# Escorna_CPU_2_00.net
KiCad netlist of a schematic drawn in EAGLE
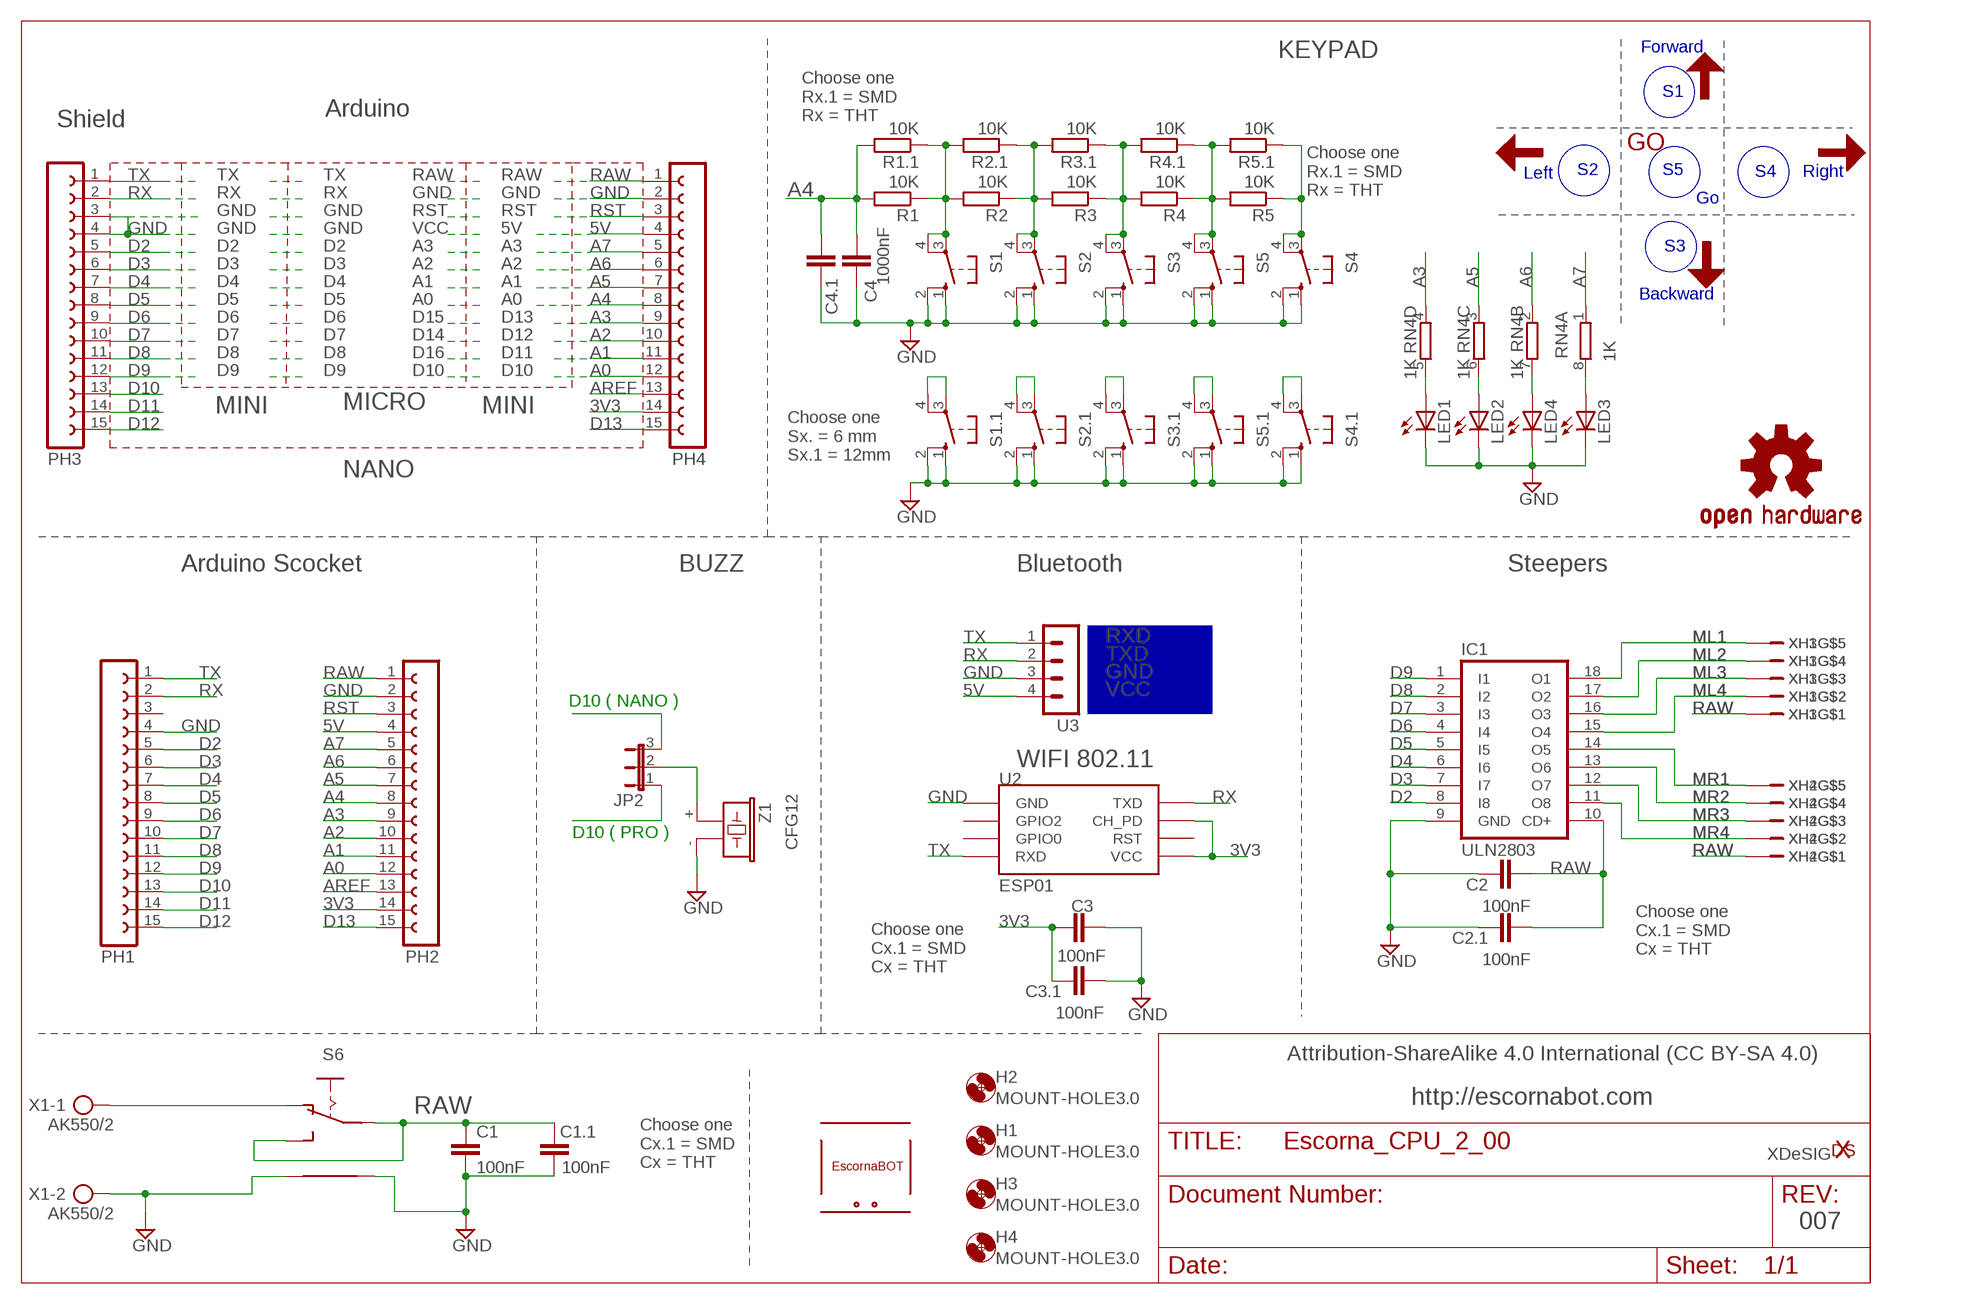
[diagram p0: schematic, sheet 1]

(export (version "E")
  (design (tool "Eeschema 10.0.6"))
  (components
    (comp (ref "C1")
      (value "100nF")
      (footprint "eagle-import:C025-025X050")
      (libsource (lib "eagle-import") (part "C-EU025-025X050"))
    )
    (comp (ref "C1.1")
      (value "100nF")
      (footprint "eagle-import:C0603")
      (libsource (lib "eagle-import") (part "C-EUC0603"))
    )
    (comp (ref "C2")
      (value "100nF")
      (footprint "eagle-import:C025-025X050")
      (libsource (lib "eagle-import") (part "C-EU025-025X050"))
    )
    (comp (ref "C2.1")
      (value "100nF")
      (footprint "eagle-import:C0603")
      (libsource (lib "eagle-import") (part "C-EUC0603"))
    )
    (comp (ref "C3")
      (value "100nF")
      (footprint "eagle-import:C025-025X050")
      (libsource (lib "eagle-import") (part "C-EU025-025X050"))
    )
    (comp (ref "C3.1")
      (value "100nF")
      (footprint "eagle-import:C0603")
      (libsource (lib "eagle-import") (part "C-EUC0603"))
    )
    (comp (ref "C4")
      (value "1000nF")
      (footprint "eagle-import:C025-025X050")
      (libsource (lib "eagle-import") (part "C-EU025-025X050"))
    )
    (comp (ref "C4.1")
      (value "100nF")
      (footprint "eagle-import:C0603")
      (libsource (lib "eagle-import") (part "C-EUC0603"))
    )
    (comp (ref "ESC")
      (value "ESCORNABOT")
      (footprint "eagle-import:ESCORNA_PEQUE")
      (libsource (lib "eagle-import") (part "ESCORNABOT"))
    )
    (comp (ref "H1")
      (value "MOUNT-HOLE3.0")
      (footprint "eagle-import:3,0")
      (libsource (lib "eagle-import") (part "MOUNT-HOLE3.0"))
    )
    (comp (ref "H2")
      (value "MOUNT-HOLE3.0")
      (footprint "eagle-import:3,0")
      (libsource (lib "eagle-import") (part "MOUNT-HOLE3.0"))
    )
    (comp (ref "H3")
      (value "MOUNT-HOLE3.0")
      (footprint "eagle-import:3,0")
      (libsource (lib "eagle-import") (part "MOUNT-HOLE3.0"))
    )
    (comp (ref "H4")
      (value "MOUNT-HOLE3.0")
      (footprint "eagle-import:3,0")
      (libsource (lib "eagle-import") (part "MOUNT-HOLE3.0"))
    )
    (comp (ref "IC1")
      (value "ULN2803")
      (footprint "eagle-import:DIL18")
      (libsource (lib "eagle-import") (part "ULN2803A{dblquote}"))
    )
    (comp (ref "JP2")
      (value "JP2E")
      (footprint "eagle-import:JP2")
      (libsource (lib "eagle-import") (part "JP2E"))
    )
    (comp (ref "LED1")
      (value "LED_ESML0603")
      (footprint "eagle-import:LED_SML0603")
      (libsource (lib "eagle-import") (part "LED_ESML0603"))
    )
    (comp (ref "LED2")
      (value "LED_ESML0603")
      (footprint "eagle-import:LED_SML0603")
      (libsource (lib "eagle-import") (part "LED_ESML0603"))
    )
    (comp (ref "LED3")
      (value "LED_ESML0603")
      (footprint "eagle-import:LED_SML0603")
      (libsource (lib "eagle-import") (part "LED_ESML0603"))
    )
    (comp (ref "LED4")
      (value "LED_ESML0603")
      (footprint "eagle-import:LED_SML0603")
      (libsource (lib "eagle-import") (part "LED_ESML0603"))
    )
    (comp (ref "LOGO1")
      (value "OSHW-LOGOS")
      (footprint "eagle-import:OSHW-LOGO-S")
      (libsource (lib "eagle-import") (part "OSHW-LOGOS"))
    )
    (comp (ref "PH1")
      (value "FE15-1")
      (footprint "eagle-import:FE15")
      (libsource (lib "eagle-import") (part "FE15-1"))
    )
    (comp (ref "PH2")
      (value "FE15-1")
      (footprint "eagle-import:FE15")
      (libsource (lib "eagle-import") (part "FE15-1"))
    )
    (comp (ref "PH3")
      (value "FE15-1")
      (footprint "eagle-import:FE15")
      (libsource (lib "eagle-import") (part "FE15-1"))
    )
    (comp (ref "PH4")
      (value "FE15-1")
      (footprint "eagle-import:FE15")
      (libsource (lib "eagle-import") (part "FE15-1"))
    )
    (comp (ref "R1")
      (value "10K")
      (footprint "eagle-import:0204_7")
      (libsource (lib "eagle-import") (part "R-EU_0204/7"))
    )
    (comp (ref "R1.1")
      (value "10K")
      (footprint "eagle-import:R0603")
      (libsource (lib "eagle-import") (part "R-EU_R0603"))
    )
    (comp (ref "R2")
      (value "10K")
      (footprint "eagle-import:0204_7")
      (libsource (lib "eagle-import") (part "R-EU_0204/7"))
    )
    (comp (ref "R2.1")
      (value "10K")
      (footprint "eagle-import:R0603")
      (libsource (lib "eagle-import") (part "R-EU_R0603"))
    )
    (comp (ref "R3")
      (value "10K")
      (footprint "eagle-import:0204_7")
      (libsource (lib "eagle-import") (part "R-EU_0204/7"))
    )
    (comp (ref "R3.1")
      (value "10K")
      (footprint "eagle-import:R0603")
      (libsource (lib "eagle-import") (part "R-EU_R0603"))
    )
    (comp (ref "R4")
      (value "10K")
      (footprint "eagle-import:0204_7")
      (libsource (lib "eagle-import") (part "R-EU_0204/7"))
    )
    (comp (ref "R4.1")
      (value "10K")
      (footprint "eagle-import:R0603")
      (libsource (lib "eagle-import") (part "R-EU_R0603"))
    )
    (comp (ref "R5")
      (value "10K")
      (footprint "eagle-import:0204_7")
      (libsource (lib "eagle-import") (part "R-EU_0204/7"))
    )
    (comp (ref "R5.1")
      (value "10K")
      (footprint "eagle-import:R0603")
      (libsource (lib "eagle-import") (part "R-EU_R0603"))
    )
    (comp (ref "RN4")
      (value "1K")
      (footprint "eagle-import:CAY16")
      (libsource (lib "eagle-import") (part "4R-NCAY16"))
    )
    (comp (ref "S1")
      (value "10-XX")
      (footprint "eagle-import:B3F-10XX")
      (fields (field (name "MPN") "B3F-1000"))
      (libsource (lib "eagle-import") (part "10-XX"))
    )
    (comp (ref "S1.1")
      (value "40-XX")
      (footprint "eagle-import:B3F40XX_NH")
      (libsource (lib "eagle-import") (part "40-XX"))
    )
    (comp (ref "S2")
      (value "10-XX")
      (footprint "eagle-import:B3F-10XX")
      (fields (field (name "MPN") "B3F-1000"))
      (libsource (lib "eagle-import") (part "10-XX"))
    )
    (comp (ref "S2.1")
      (value "40-XX")
      (footprint "eagle-import:B3F40XX_NH")
      (libsource (lib "eagle-import") (part "40-XX"))
    )
    (comp (ref "S3")
      (value "10-XX")
      (footprint "eagle-import:B3F-10XX")
      (fields (field (name "MPN") "B3F-1000"))
      (libsource (lib "eagle-import") (part "10-XX"))
    )
    (comp (ref "S3.1")
      (value "40-XX")
      (footprint "eagle-import:B3F40XX_NH")
      (libsource (lib "eagle-import") (part "40-XX"))
    )
    (comp (ref "S4")
      (value "10-XX")
      (footprint "eagle-import:B3F-10XX")
      (fields (field (name "MPN") "B3F-1000"))
      (libsource (lib "eagle-import") (part "10-XX"))
    )
    (comp (ref "S4.1")
      (value "40-XX")
      (footprint "eagle-import:B3F40XX_NH")
      (libsource (lib "eagle-import") (part "40-XX"))
    )
    (comp (ref "S5")
      (value "10-XX")
      (footprint "eagle-import:B3F-10XX")
      (fields (field (name "MPN") "B3F-1000"))
      (libsource (lib "eagle-import") (part "10-XX"))
    )
    (comp (ref "S5.1")
      (value "40-XX")
      (footprint "eagle-import:B3F40XX_NH")
      (libsource (lib "eagle-import") (part "40-XX"))
    )
    (comp (ref "S6")
      (value "SK12F14D")
      (footprint "eagle-import:SK-12D07")
      (libsource (lib "eagle-import") (part "SK12F14D"))
    )
    (comp (ref "U$4")
      (value "FRECHA")
      (footprint "eagle-import:FRECHA")
      (libsource (lib "eagle-import") (part "FRECHA"))
    )
    (comp (ref "U$7")
      (value "FRECHA")
      (footprint "eagle-import:FRECHA")
      (libsource (lib "eagle-import") (part "FRECHA"))
    )
    (comp (ref "U$8")
      (value "FRECHA")
      (footprint "eagle-import:FRECHA")
      (libsource (lib "eagle-import") (part "FRECHA"))
    )
    (comp (ref "U$9")
      (value "FRECHA")
      (footprint "eagle-import:FRECHA")
      (libsource (lib "eagle-import") (part "FRECHA"))
    )
    (comp (ref "U$10")
      (value "GO")
      (footprint "eagle-import:VALE")
      (libsource (lib "eagle-import") (part "GO"))
    )
    (comp (ref "U2")
      (value "ESP01")
      (footprint "eagle-import:ESP01")
      (libsource (lib "eagle-import") (part "ESP01"))
    )
    (comp (ref "U3")
      (value "MA04-1")
      (footprint "eagle-import:MA04-1")
      (libsource (lib "eagle-import") (part "MA04-1"))
    )
    (comp (ref "X1")
      (value "AK550/2")
      (footprint "eagle-import:AK550_2")
      (libsource (lib "eagle-import") (part "AK550/2"))
    )
    (comp (ref "XDS1")
      (value "XDESIG")
      (footprint "eagle-import:XDESIG_CU_2")
      (libsource (lib "eagle-import") (part "XDESIG"))
    )
    (comp (ref "XH1")
      (value "B5B-XH-A")
      (footprint "eagle-import:B5B-XH-A")
      (libsource (lib "eagle-import") (part "B5B-XH-A"))
    )
    (comp (ref "XH2")
      (value "B5B-XH-A")
      (footprint "eagle-import:B5B-XH-A")
      (libsource (lib "eagle-import") (part "B5B-XH-A"))
    )
    (comp (ref "XH3")
      (value "B5B-XH-A")
      (footprint "eagle-import:B5B-XH-A")
      (libsource (lib "eagle-import") (part "B5B-XH-A"))
    )
    (comp (ref "XH4")
      (value "B5B-XH-A")
      (footprint "eagle-import:B5B-XH-A")
      (libsource (lib "eagle-import") (part "B5B-XH-A"))
    )
    (comp (ref "Z1")
      (value "CFG12")
      (footprint "eagle-import:F_CM12P")
      (libsource (lib "eagle-import") (part "F/CM12P"))
    )
  )
  (nets
    (net (code "1") (name "/3V3") (class "Default")
      (node (ref "C3") (pin "1") (pinfunction "1_1") (pintype "passive"))
      (node (ref "C3.1") (pin "1") (pinfunction "1_1") (pintype "passive"))
      (node (ref "PH2") (pin "14") (pinfunction "14_14") (pintype "passive"))
      (node (ref "PH4") (pin "14") (pinfunction "14_14") (pintype "passive"))
      (node (ref "U2") (pin "CH_PD") (pinfunction "CH_PD_CH_PD") (pintype "bidirectional"))
      (node (ref "U2") (pin "VCC") (pinfunction "VCC_VCC") (pintype "bidirectional"))
    )
    (net (code "2") (name "/5V") (class "Default")
      (node (ref "PH2") (pin "4") (pinfunction "4_4") (pintype "passive"))
      (node (ref "PH4") (pin "4") (pinfunction "4_4") (pintype "passive"))
      (node (ref "U3") (pin "4") (pinfunction "4_4") (pintype "passive"))
    )
    (net (code "3") (name "/A0") (class "Default")
      (node (ref "JP2") (pin "1") (pinfunction "1_1") (pintype "passive"))
      (node (ref "PH2") (pin "12") (pinfunction "12_12") (pintype "passive"))
      (node (ref "PH4") (pin "12") (pinfunction "12_12") (pintype "passive"))
    )
    (net (code "4") (name "/A1") (class "Default")
      (node (ref "PH2") (pin "11") (pinfunction "11_11") (pintype "passive"))
      (node (ref "PH4") (pin "11") (pinfunction "11_11") (pintype "passive"))
    )
    (net (code "5") (name "/A2") (class "Default")
      (node (ref "PH2") (pin "10") (pinfunction "10_10") (pintype "passive"))
      (node (ref "PH4") (pin "10") (pinfunction "10_10") (pintype "passive"))
    )
    (net (code "6") (name "/A3") (class "Default")
      (node (ref "PH2") (pin "9") (pinfunction "9_9") (pintype "passive"))
      (node (ref "PH4") (pin "9") (pinfunction "9_9") (pintype "passive"))
      (node (ref "RN4") (pin "4") (pinfunction "1_4") (pintype "passive"))
    )
    (net (code "7") (name "/A4") (class "Default")
      (node (ref "C4") (pin "2") (pinfunction "2_2") (pintype "passive"))
      (node (ref "C4.1") (pin "2") (pinfunction "2_2") (pintype "passive"))
      (node (ref "PH2") (pin "8") (pinfunction "8_8") (pintype "passive"))
      (node (ref "PH4") (pin "8") (pinfunction "8_8") (pintype "passive"))
      (node (ref "R1") (pin "2") (pinfunction "2_2") (pintype "passive"))
      (node (ref "R1.1") (pin "2") (pinfunction "2_2") (pintype "passive"))
    )
    (net (code "8") (name "/A5") (class "Default")
      (node (ref "PH2") (pin "7") (pinfunction "7_7") (pintype "passive"))
      (node (ref "PH4") (pin "7") (pinfunction "7_7") (pintype "passive"))
      (node (ref "RN4") (pin "3") (pinfunction "1_3") (pintype "passive"))
    )
    (net (code "9") (name "/A6") (class "Default")
      (node (ref "PH2") (pin "6") (pinfunction "6_6") (pintype "passive"))
      (node (ref "PH4") (pin "6") (pinfunction "6_6") (pintype "passive"))
      (node (ref "RN4") (pin "2") (pinfunction "1_2") (pintype "passive"))
    )
    (net (code "10") (name "/A7") (class "Default")
      (node (ref "PH2") (pin "5") (pinfunction "5_5") (pintype "passive"))
      (node (ref "PH4") (pin "5") (pinfunction "5_5") (pintype "passive"))
      (node (ref "RN4") (pin "1") (pinfunction "1_1") (pintype "passive"))
    )
    (net (code "11") (name "/AREF") (class "Default")
      (node (ref "PH2") (pin "13") (pinfunction "13_13") (pintype "passive"))
      (node (ref "PH4") (pin "13") (pinfunction "13_13") (pintype "passive"))
    )
    (net (code "12") (name "/D2") (class "Default")
      (node (ref "IC1") (pin "8") (pinfunction "I8_8") (pintype "input"))
      (node (ref "PH1") (pin "5") (pinfunction "5_5") (pintype "passive"))
      (node (ref "PH3") (pin "5") (pinfunction "5_5") (pintype "passive"))
    )
    (net (code "13") (name "/D3") (class "Default")
      (node (ref "IC1") (pin "7") (pinfunction "I7_7") (pintype "input"))
      (node (ref "PH1") (pin "6") (pinfunction "6_6") (pintype "passive"))
      (node (ref "PH3") (pin "6") (pinfunction "6_6") (pintype "passive"))
    )
    (net (code "14") (name "/D4") (class "Default")
      (node (ref "IC1") (pin "6") (pinfunction "I6_6") (pintype "input"))
      (node (ref "PH1") (pin "7") (pinfunction "7_7") (pintype "passive"))
      (node (ref "PH3") (pin "7") (pinfunction "7_7") (pintype "passive"))
    )
    (net (code "15") (name "/D5") (class "Default")
      (node (ref "IC1") (pin "5") (pinfunction "I5_5") (pintype "input"))
      (node (ref "PH1") (pin "8") (pinfunction "8_8") (pintype "passive"))
      (node (ref "PH3") (pin "8") (pinfunction "8_8") (pintype "passive"))
    )
    (net (code "16") (name "/D6") (class "Default")
      (node (ref "IC1") (pin "4") (pinfunction "I4_4") (pintype "input"))
      (node (ref "PH1") (pin "9") (pinfunction "9_9") (pintype "passive"))
      (node (ref "PH3") (pin "9") (pinfunction "9_9") (pintype "passive"))
    )
    (net (code "17") (name "/D7") (class "Default")
      (node (ref "IC1") (pin "3") (pinfunction "I3_3") (pintype "input"))
      (node (ref "PH1") (pin "10") (pinfunction "10_10") (pintype "passive"))
      (node (ref "PH3") (pin "10") (pinfunction "10_10") (pintype "passive"))
    )
    (net (code "18") (name "/D8") (class "Default")
      (node (ref "IC1") (pin "2") (pinfunction "I2_2") (pintype "input"))
      (node (ref "PH1") (pin "11") (pinfunction "11_11") (pintype "passive"))
      (node (ref "PH3") (pin "11") (pinfunction "11_11") (pintype "passive"))
    )
    (net (code "19") (name "/D9") (class "Default")
      (node (ref "IC1") (pin "1") (pinfunction "I1_1") (pintype "input"))
      (node (ref "PH1") (pin "12") (pinfunction "12_12") (pintype "passive"))
      (node (ref "PH3") (pin "12") (pinfunction "12_12") (pintype "passive"))
    )
    (net (code "20") (name "/D10") (class "Default")
      (node (ref "JP2") (pin "3") (pinfunction "3_3") (pintype "passive"))
      (node (ref "PH1") (pin "13") (pinfunction "13_13") (pintype "passive"))
      (node (ref "PH3") (pin "13") (pinfunction "13_13") (pintype "passive"))
    )
    (net (code "21") (name "/D11") (class "Default")
      (node (ref "PH1") (pin "14") (pinfunction "14_14") (pintype "passive"))
      (node (ref "PH3") (pin "14") (pinfunction "14_14") (pintype "passive"))
    )
    (net (code "22") (name "/D12") (class "Default")
      (node (ref "PH1") (pin "15") (pinfunction "15_15") (pintype "passive"))
      (node (ref "PH3") (pin "15") (pinfunction "15_15") (pintype "passive"))
    )
    (net (code "23") (name "/D13") (class "Default")
      (node (ref "PH2") (pin "15") (pinfunction "15_15") (pintype "passive"))
      (node (ref "PH4") (pin "15") (pinfunction "15_15") (pintype "passive"))
    )
    (net (code "24") (name "/ML1") (class "Default")
      (node (ref "IC1") (pin "18") (pinfunction "O1_18") (pintype "open_collector"))
      (node (ref "XH1") (pin "P$5") (pinfunction "1_P$5") (pintype "passive"))
      (node (ref "XH3") (pin "P$5") (pinfunction "1_P$5") (pintype "passive"))
    )
    (net (code "25") (name "/ML2") (class "Default")
      (node (ref "IC1") (pin "17") (pinfunction "O2_17") (pintype "open_collector"))
      (node (ref "XH1") (pin "P$4") (pinfunction "1_P$4") (pintype "passive"))
      (node (ref "XH3") (pin "P$4") (pinfunction "1_P$4") (pintype "passive"))
    )
    (net (code "26") (name "/ML3") (class "Default")
      (node (ref "IC1") (pin "16") (pinfunction "O3_16") (pintype "open_collector"))
      (node (ref "XH1") (pin "P$3") (pinfunction "1_P$3") (pintype "passive"))
      (node (ref "XH3") (pin "P$3") (pinfunction "1_P$3") (pintype "passive"))
    )
    (net (code "27") (name "/ML4") (class "Default")
      (node (ref "IC1") (pin "15") (pinfunction "O4_15") (pintype "open_collector"))
      (node (ref "XH1") (pin "P$2") (pinfunction "1_P$2") (pintype "passive"))
      (node (ref "XH3") (pin "P$2") (pinfunction "1_P$2") (pintype "passive"))
    )
    (net (code "28") (name "/MR1") (class "Default")
      (node (ref "IC1") (pin "14") (pinfunction "O5_14") (pintype "open_collector"))
      (node (ref "XH2") (pin "P$5") (pinfunction "1_P$5") (pintype "passive"))
      (node (ref "XH4") (pin "P$5") (pinfunction "1_P$5") (pintype "passive"))
    )
    (net (code "29") (name "/MR2") (class "Default")
      (node (ref "IC1") (pin "13") (pinfunction "O6_13") (pintype "open_collector"))
      (node (ref "XH2") (pin "P$4") (pinfunction "1_P$4") (pintype "passive"))
      (node (ref "XH4") (pin "P$4") (pinfunction "1_P$4") (pintype "passive"))
    )
    (net (code "30") (name "/MR3") (class "Default")
      (node (ref "IC1") (pin "12") (pinfunction "O7_12") (pintype "open_collector"))
      (node (ref "XH2") (pin "P$3") (pinfunction "1_P$3") (pintype "passive"))
      (node (ref "XH4") (pin "P$3") (pinfunction "1_P$3") (pintype "passive"))
    )
    (net (code "31") (name "/MR4") (class "Default")
      (node (ref "IC1") (pin "11") (pinfunction "O8_11") (pintype "open_collector"))
      (node (ref "XH2") (pin "P$2") (pinfunction "1_P$2") (pintype "passive"))
      (node (ref "XH4") (pin "P$2") (pinfunction "1_P$2") (pintype "passive"))
    )
    (net (code "32") (name "/RAW") (class "Default")
      (node (ref "C1") (pin "1") (pinfunction "1_1") (pintype "passive"))
      (node (ref "C1.1") (pin "2") (pinfunction "2_2") (pintype "passive"))
      (node (ref "C2") (pin "2") (pinfunction "2_2") (pintype "passive"))
      (node (ref "C2.1") (pin "2") (pinfunction "2_2") (pintype "passive"))
      (node (ref "IC1") (pin "10") (pinfunction "CD+_10") (pintype "passive"))
      (node (ref "PH2") (pin "1") (pinfunction "1_1") (pintype "passive"))
      (node (ref "PH4") (pin "1") (pinfunction "1_1") (pintype "passive"))
      (node (ref "S6") (pin "P$1") (pinfunction "P_P$1") (pintype "passive"))
      (node (ref "S6") (pin "P$3") (pinfunction "S_P$3") (pintype "passive"))
      (node (ref "XH1") (pin "P$1") (pinfunction "1_P$1") (pintype "passive"))
      (node (ref "XH2") (pin "P$1") (pinfunction "1_P$1") (pintype "passive"))
      (node (ref "XH3") (pin "P$1") (pinfunction "1_P$1") (pintype "passive"))
      (node (ref "XH4") (pin "P$1") (pinfunction "1_P$1") (pintype "passive"))
    )
    (net (code "33") (name "/RST") (class "Default")
      (node (ref "PH2") (pin "3") (pinfunction "3_3") (pintype "passive"))
      (node (ref "PH4") (pin "3") (pinfunction "3_3") (pintype "passive"))
    )
    (net (code "34") (name "/RX") (class "Default")
      (node (ref "PH1") (pin "2") (pinfunction "2_2") (pintype "passive"))
      (node (ref "PH3") (pin "2") (pinfunction "2_2") (pintype "passive"))
      (node (ref "U2") (pin "TX") (pinfunction "TXD_TX") (pintype "bidirectional"))
      (node (ref "U3") (pin "2") (pinfunction "2_2") (pintype "passive"))
    )
    (net (code "35") (name "/S1") (class "Default")
      (node (ref "R1") (pin "1") (pinfunction "1_1") (pintype "passive"))
      (node (ref "R1.1") (pin "1") (pinfunction "1_1") (pintype "passive"))
      (node (ref "R2") (pin "2") (pinfunction "2_2") (pintype "passive"))
      (node (ref "R2.1") (pin "2") (pinfunction "2_2") (pintype "passive"))
      (node (ref "S1") (pin "3") (pinfunction "P_3") (pintype "passive"))
      (node (ref "S1") (pin "4") (pinfunction "P1_4") (pintype "passive"))
      (node (ref "S1.1") (pin "3") (pinfunction "P_3") (pintype "passive"))
      (node (ref "S1.1") (pin "4") (pinfunction "P1_4") (pintype "passive"))
    )
    (net (code "36") (name "/S2") (class "Default")
      (node (ref "R2") (pin "1") (pinfunction "1_1") (pintype "passive"))
      (node (ref "R2.1") (pin "1") (pinfunction "1_1") (pintype "passive"))
      (node (ref "R3") (pin "2") (pinfunction "2_2") (pintype "passive"))
      (node (ref "R3.1") (pin "2") (pinfunction "2_2") (pintype "passive"))
      (node (ref "S2") (pin "3") (pinfunction "P_3") (pintype "passive"))
      (node (ref "S2") (pin "4") (pinfunction "P1_4") (pintype "passive"))
      (node (ref "S2.1") (pin "3") (pinfunction "P_3") (pintype "passive"))
      (node (ref "S2.1") (pin "4") (pinfunction "P1_4") (pintype "passive"))
    )
    (net (code "37") (name "/S3") (class "Default")
      (node (ref "R3") (pin "1") (pinfunction "1_1") (pintype "passive"))
      (node (ref "R3.1") (pin "1") (pinfunction "1_1") (pintype "passive"))
      (node (ref "R4") (pin "2") (pinfunction "2_2") (pintype "passive"))
      (node (ref "R4.1") (pin "2") (pinfunction "2_2") (pintype "passive"))
      (node (ref "S3") (pin "3") (pinfunction "P_3") (pintype "passive"))
      (node (ref "S3") (pin "4") (pinfunction "P1_4") (pintype "passive"))
      (node (ref "S3.1") (pin "3") (pinfunction "P_3") (pintype "passive"))
      (node (ref "S3.1") (pin "4") (pinfunction "P1_4") (pintype "passive"))
    )
    (net (code "38") (name "/S4") (class "Default")
      (node (ref "R4") (pin "1") (pinfunction "1_1") (pintype "passive"))
      (node (ref "R4.1") (pin "1") (pinfunction "1_1") (pintype "passive"))
      (node (ref "R5") (pin "2") (pinfunction "2_2") (pintype "passive"))
      (node (ref "R5.1") (pin "2") (pinfunction "2_2") (pintype "passive"))
      (node (ref "S5") (pin "3") (pinfunction "P_3") (pintype "passive"))
      (node (ref "S5") (pin "4") (pinfunction "P1_4") (pintype "passive"))
      (node (ref "S5.1") (pin "3") (pinfunction "P_3") (pintype "passive"))
      (node (ref "S5.1") (pin "4") (pinfunction "P1_4") (pintype "passive"))
    )
    (net (code "39") (name "/S5") (class "Default")
      (node (ref "R5") (pin "1") (pinfunction "1_1") (pintype "passive"))
      (node (ref "R5.1") (pin "1") (pinfunction "1_1") (pintype "passive"))
      (node (ref "S4") (pin "3") (pinfunction "P_3") (pintype "passive"))
      (node (ref "S4") (pin "4") (pinfunction "P1_4") (pintype "passive"))
      (node (ref "S4.1") (pin "3") (pinfunction "P_3") (pintype "passive"))
      (node (ref "S4.1") (pin "4") (pinfunction "P1_4") (pintype "passive"))
    )
    (net (code "40") (name "/TX") (class "Default")
      (node (ref "PH1") (pin "1") (pinfunction "1_1") (pintype "passive"))
      (node (ref "PH3") (pin "1") (pinfunction "1_1") (pintype "passive"))
      (node (ref "U2") (pin "RX") (pinfunction "RXD_RX") (pintype "bidirectional"))
      (node (ref "U3") (pin "1") (pinfunction "1_1") (pintype "passive"))
    )
    (net (code "41") (name "GND") (class "Default")
      (node (ref "C1") (pin "2") (pinfunction "2_2") (pintype "passive"))
      (node (ref "C1.1") (pin "1") (pinfunction "1_1") (pintype "passive"))
      (node (ref "C2") (pin "1") (pinfunction "1_1") (pintype "passive"))
      (node (ref "C2.1") (pin "1") (pinfunction "1_1") (pintype "passive"))
      (node (ref "C3") (pin "2") (pinfunction "2_2") (pintype "passive"))
      (node (ref "C3.1") (pin "2") (pinfunction "2_2") (pintype "passive"))
      (node (ref "C4") (pin "1") (pinfunction "1_1") (pintype "passive"))
      (node (ref "C4.1") (pin "1") (pinfunction "1_1") (pintype "passive"))
      (node (ref "IC1") (pin "9") (pinfunction "GND_9") (pintype "power_in"))
      (node (ref "LED1") (pin "C") (pinfunction "C_C") (pintype "passive"))
      (node (ref "LED2") (pin "C") (pinfunction "C_C") (pintype "passive"))
      (node (ref "LED3") (pin "C") (pinfunction "C_C") (pintype "passive"))
      (node (ref "LED4") (pin "C") (pinfunction "C_C") (pintype "passive"))
      (node (ref "PH1") (pin "4") (pinfunction "4_4") (pintype "passive"))
      (node (ref "PH2") (pin "2") (pinfunction "2_2") (pintype "passive"))
      (node (ref "PH3") (pin "3") (pinfunction "3_3") (pintype "passive"))
      (node (ref "PH3") (pin "4") (pinfunction "4_4") (pintype "passive"))
      (node (ref "PH4") (pin "2") (pinfunction "2_2") (pintype "passive"))
      (node (ref "S1") (pin "1") (pinfunction "S_1") (pintype "passive"))
      (node (ref "S1") (pin "2") (pinfunction "S1_2") (pintype "passive"))
      (node (ref "S1.1") (pin "1") (pinfunction "S_1") (pintype "passive"))
      (node (ref "S1.1") (pin "2") (pinfunction "S1_2") (pintype "passive"))
      (node (ref "S2") (pin "1") (pinfunction "S_1") (pintype "passive"))
      (node (ref "S2") (pin "2") (pinfunction "S1_2") (pintype "passive"))
      (node (ref "S2.1") (pin "1") (pinfunction "S_1") (pintype "passive"))
      (node (ref "S2.1") (pin "2") (pinfunction "S1_2") (pintype "passive"))
      (node (ref "S3") (pin "1") (pinfunction "S_1") (pintype "passive"))
      (node (ref "S3") (pin "2") (pinfunction "S1_2") (pintype "passive"))
      (node (ref "S3.1") (pin "1") (pinfunction "S_1") (pintype "passive"))
      (node (ref "S3.1") (pin "2") (pinfunction "S1_2") (pintype "passive"))
      (node (ref "S4") (pin "1") (pinfunction "S_1") (pintype "passive"))
      (node (ref "S4") (pin "2") (pinfunction "S1_2") (pintype "passive"))
      (node (ref "S4.1") (pin "1") (pinfunction "S_1") (pintype "passive"))
      (node (ref "S4.1") (pin "2") (pinfunction "S1_2") (pintype "passive"))
      (node (ref "S5") (pin "1") (pinfunction "S_1") (pintype "passive"))
      (node (ref "S5") (pin "2") (pinfunction "S1_2") (pintype "passive"))
      (node (ref "S5.1") (pin "1") (pinfunction "S_1") (pintype "passive"))
      (node (ref "S5.1") (pin "2") (pinfunction "S1_2") (pintype "passive"))
      (node (ref "S6") (pin "P$4") (pinfunction "P$1_P$4") (pintype "passive"))
      (node (ref "S6") (pin "P$5") (pinfunction "P$2_P$5") (pintype "bidirectional"))
      (node (ref "U2") (pin "GND") (pinfunction "GND_GND") (pintype "bidirectional"))
      (node (ref "U3") (pin "3") (pinfunction "3_3") (pintype "passive"))
      (node (ref "X1") (pin "2") (pinfunction "KL_2") (pintype "passive"))
      (node (ref "Z1") (pin "-") (pinfunction "2_-") (pintype "passive"))
    )
    (net (code "42") (name "Net-(RN4A-2)") (class "Default")
      (node (ref "LED3") (pin "A") (pinfunction "A_A") (pintype "passive"))
      (node (ref "RN4") (pin "8") (pinfunction "2_8") (pintype "passive"))
    )
    (net (code "43") (name "Net-(RN4B-2)") (class "Default")
      (node (ref "LED4") (pin "A") (pinfunction "A_A") (pintype "passive"))
      (node (ref "RN4") (pin "7") (pinfunction "2_7") (pintype "passive"))
    )
    (net (code "44") (name "Net-(RN4C-2)") (class "Default")
      (node (ref "LED2") (pin "A") (pinfunction "A_A") (pintype "passive"))
      (node (ref "RN4") (pin "6") (pinfunction "2_6") (pintype "passive"))
    )
    (net (code "45") (name "Net-(RN4D-2)") (class "Default")
      (node (ref "LED1") (pin "A") (pinfunction "A_A") (pintype "passive"))
      (node (ref "RN4") (pin "5") (pinfunction "2_5") (pintype "passive"))
    )
    (net (code "46") (name "Net-(S6-O)") (class "Default")
      (node (ref "S6") (pin "P$2") (pinfunction "O_P$2") (pintype "passive"))
      (node (ref "X1") (pin "1") (pinfunction "KL_1") (pintype "passive"))
    )
    (net (code "47") (name "Net-(Z1-1)") (class "Default")
      (node (ref "JP2") (pin "2") (pinfunction "2_2") (pintype "passive"))
      (node (ref "Z1") (pin "+") (pinfunction "1_+") (pintype "passive"))
    )
    (net (code "48") (name "unconnected-(PH1-Pad3)") (class "Default")
      (node (ref "PH1") (pin "3") (pinfunction "3_3") (pintype "passive"))
    )
    (net (code "49") (name "unconnected-(U2-PadGPIO0)") (class "Default")
      (node (ref "U2") (pin "GPIO0") (pinfunction "GPIO0_GPIO0") (pintype "bidirectional"))
    )
    (net (code "50") (name "unconnected-(U2-PadGPIO2)") (class "Default")
      (node (ref "U2") (pin "GPIO2") (pinfunction "GPIO2_GPIO2") (pintype "bidirectional"))
    )
    (net (code "51") (name "unconnected-(U2-PadRST)") (class "Default")
      (node (ref "U2") (pin "RST") (pinfunction "RST_RST") (pintype "bidirectional"))
    )
  )
)
